# Cap_Switch.net
KiCad netlist of a schematic drawn in EAGLE
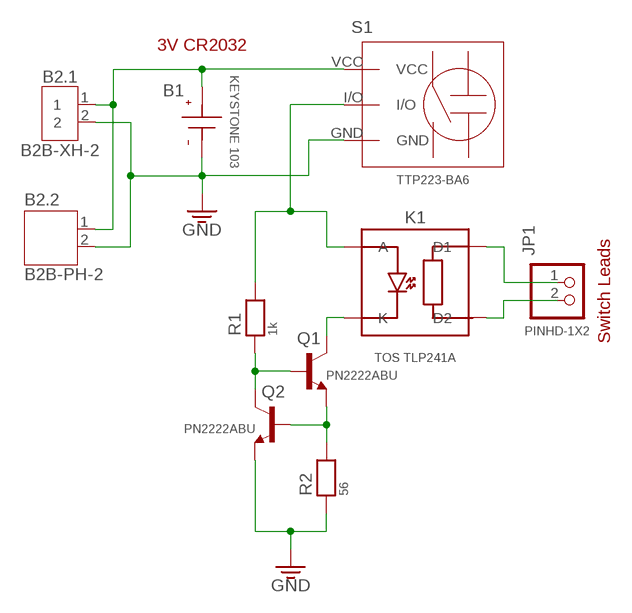
[diagram p0: schematic, sheet 1]

(export (version "E")
  (design (tool "Eeschema 10.0.6"))
  (components
    (comp (ref "B1")
      (value "KEYSTONE 103")
      (footprint "eagle-import:1026_KEY-103")
      (fields
        (field (name "MANUFACTURER_PART_NUMBER") "1026")
        (field (name "COPYRIGHT") "Copyright (C) 2022 Ultra Librarian. All rights reserved.")
      )
      (libsource (lib "eagle-import") (part "COINCELL-KEYSTONE#1026"))
    )
    (comp (ref "B2.1")
      (value "B2B-XH-2")
      (footprint "eagle-import:B2B-XH-A")
      (fields (field (name "MANUFACTURER") "JST (XH CONNECTOR)") (field (name "MPN") "B2B-XH-A"))
      (libsource (lib "eagle-import") (part "B2B-XH-A"))
    )
    (comp (ref "B2.2")
      (value "B2B-PH-2")
      (footprint "eagle-import:JST-PH2")
      (libsource (lib "eagle-import") (part "JST-PH2"))
    )
    (comp (ref "JP1")
      (value "PINHD-1X2")
      (footprint "eagle-import:1X02")
      (libsource (lib "eagle-import") (part "PINHD-1X2"))
    )
    (comp (ref "K1")
      (value "TOS TLP241A")
      (footprint "eagle-import:TOS-TLP241A")
      (libsource (lib "eagle-import") (part "RELAY-SS-TOS-TLP241-A"))
    )
    (comp (ref "Q1")
      (value "PN2222ABU")
      (footprint "eagle-import:TO92-")
      (libsource (lib "eagle-import") (part "BJT-NPN-TO-92"))
    )
    (comp (ref "Q2")
      (value "PN2222ABU")
      (footprint "eagle-import:TO92-")
      (libsource (lib "eagle-import") (part "BJT-NPN-TO-92"))
    )
    (comp (ref "R1")
      (value "1k")
      (footprint "eagle-import:1206")
      (libsource (lib "eagle-import") (part "RESISTOR1206"))
    )
    (comp (ref "R2")
      (value "56")
      (footprint "eagle-import:1206")
      (libsource (lib "eagle-import") (part "RESISTOR1206"))
    )
    (comp (ref "S1")
      (value "TTP223-BA6")
      (footprint "eagle-import:SW-CAP-TOUCH-AMZN")
      (libsource (lib "eagle-import") (part "SWITCH-CAP-TOUCH-AMZN"))
    )
  )
  (nets
    (net (code "1") (name "GND") (class "Default")
      (node (ref "B1") (pin "-") (pinfunction "NEG_-") (pintype "passive"))
      (node (ref "B2.1") (pin "2") (pinfunction "2_2") (pintype "bidirectional"))
      (node (ref "B2.2") (pin "2") (pinfunction "2_2") (pintype "passive"))
      (node (ref "Q2") (pin "1") (pinfunction "E_1") (pintype "passive"))
      (node (ref "R2") (pin "1") (pinfunction "1_1") (pintype "passive"))
      (node (ref "S1") (pin "GND") (pinfunction "GND_GND") (pintype "bidirectional"))
    )
    (net (code "2") (name "Net-(B1-POS)") (class "Default")
      (node (ref "B1") (pin "+") (pinfunction "POS_+") (pintype "passive"))
      (node (ref "B2.1") (pin "1") (pinfunction "1_1") (pintype "bidirectional"))
      (node (ref "B2.2") (pin "1") (pinfunction "1_1") (pintype "passive"))
      (node (ref "S1") (pin "VCC") (pinfunction "VCC_VCC") (pintype "bidirectional"))
    )
    (net (code "3") (name "Net-(K1-A)") (class "Default")
      (node (ref "K1") (pin "P$1") (pinfunction "A_P$1") (pintype "bidirectional"))
      (node (ref "R1") (pin "2") (pinfunction "2_2") (pintype "passive"))
      (node (ref "S1") (pin "I/O") (pinfunction "I/O_I/O") (pintype "bidirectional"))
    )
    (net (code "4") (name "Net-(K1-D1)") (class "Default")
      (node (ref "JP1") (pin "1") (pinfunction "1_1") (pintype "passive"))
      (node (ref "K1") (pin "P$4") (pinfunction "D1_P$4") (pintype "bidirectional"))
    )
    (net (code "5") (name "Net-(K1-D2)") (class "Default")
      (node (ref "JP1") (pin "2") (pinfunction "2_2") (pintype "passive"))
      (node (ref "K1") (pin "P$3") (pinfunction "D2_P$3") (pintype "bidirectional"))
    )
    (net (code "6") (name "Net-(K1-K)") (class "Default")
      (node (ref "K1") (pin "P$2") (pinfunction "K_P$2") (pintype "bidirectional"))
      (node (ref "Q1") (pin "3") (pinfunction "C_3") (pintype "passive"))
    )
    (net (code "7") (name "Net-(Q1-B)") (class "Default")
      (node (ref "Q1") (pin "2") (pinfunction "B_2") (pintype "passive"))
      (node (ref "Q2") (pin "3") (pinfunction "C_3") (pintype "passive"))
      (node (ref "R1") (pin "1") (pinfunction "1_1") (pintype "passive"))
    )
    (net (code "8") (name "Net-(Q1-E)") (class "Default")
      (node (ref "Q1") (pin "1") (pinfunction "E_1") (pintype "passive"))
      (node (ref "Q2") (pin "2") (pinfunction "B_2") (pintype "passive"))
      (node (ref "R2") (pin "2") (pinfunction "2_2") (pintype "passive"))
    )
  )
)
